# Nikon_PowerBoardV4.net
KiCad netlist of a schematic drawn in EAGLE
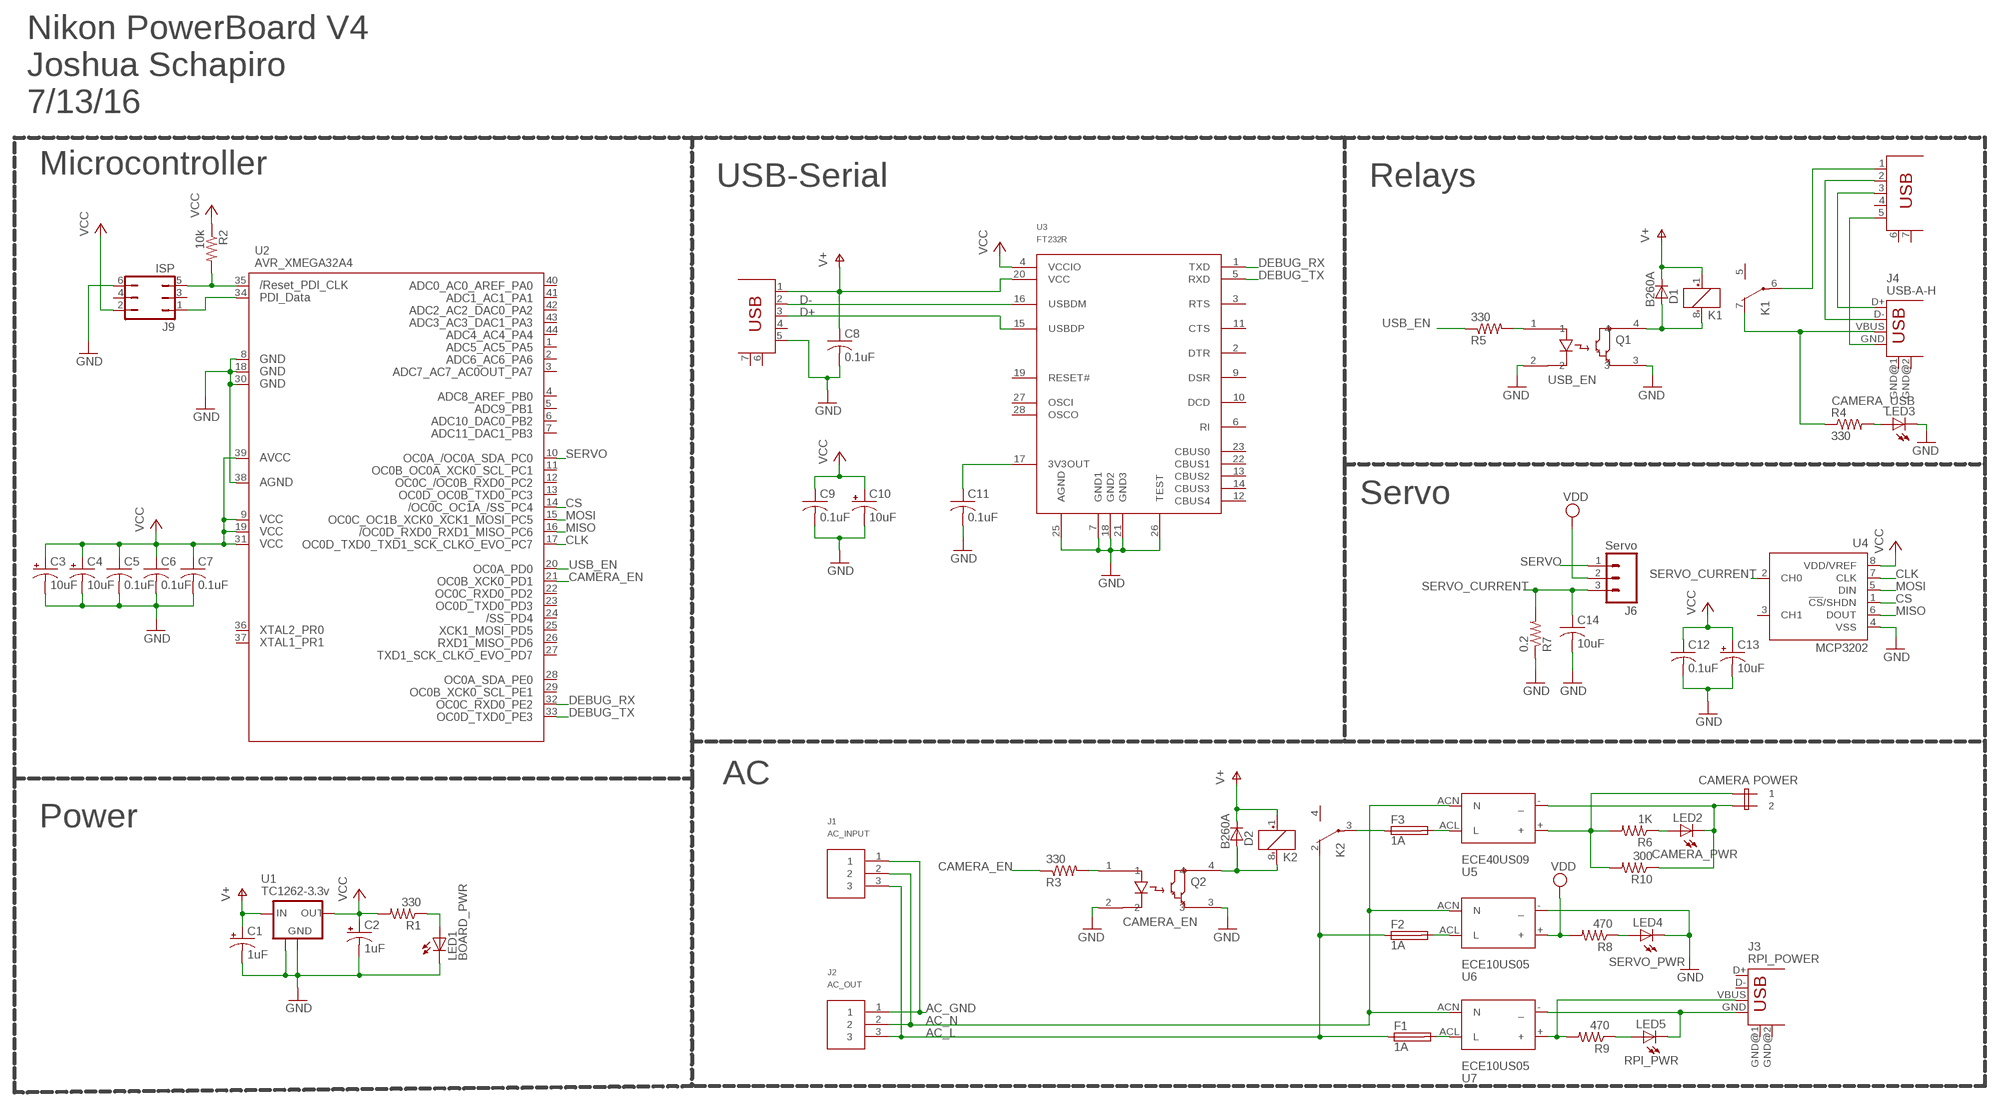
[diagram p0: schematic, sheet 1]

(export (version "E")
  (design (tool "Eeschema 10.0.6"))
  (components
    (comp (ref "C1")
      (value "1uF")
      (footprint "eagle-import:EIA3216")
      (libsource (lib "eagle-import") (part "CAP_POL1206"))
    )
    (comp (ref "C2")
      (value "1uF")
      (footprint "eagle-import:EIA3216")
      (libsource (lib "eagle-import") (part "CAP_POL1206"))
    )
    (comp (ref "C3")
      (value "10uF")
      (footprint "eagle-import:EIA3216")
      (libsource (lib "eagle-import") (part "CAP_POL1206"))
    )
    (comp (ref "C4")
      (value "10uF")
      (footprint "eagle-import:EIA3216")
      (libsource (lib "eagle-import") (part "CAP_POL1206"))
    )
    (comp (ref "C5")
      (value "0.1uF")
      (footprint "eagle-import:C0603")
      (libsource (lib "eagle-import") (part "C-USC0603"))
    )
    (comp (ref "C6")
      (value "0.1uF")
      (footprint "eagle-import:C0603")
      (libsource (lib "eagle-import") (part "resistor_C-USC0603"))
    )
    (comp (ref "C7")
      (value "0.1uF")
      (footprint "eagle-import:C0603")
      (libsource (lib "eagle-import") (part "resistor_C-USC0603"))
    )
    (comp (ref "C8")
      (value "0.1uF")
      (footprint "eagle-import:C0603")
      (libsource (lib "eagle-import") (part "resistor_C-USC0603"))
    )
    (comp (ref "C9")
      (value "0.1uF")
      (footprint "eagle-import:C0603")
      (libsource (lib "eagle-import") (part "resistor_C-USC0603"))
    )
    (comp (ref "C10")
      (value "10uF")
      (footprint "eagle-import:EIA3216")
      (libsource (lib "eagle-import") (part "CAP_POL1206"))
    )
    (comp (ref "C11")
      (value "0.1uF")
      (footprint "eagle-import:C0603")
      (libsource (lib "eagle-import") (part "resistor_C-USC0603"))
    )
    (comp (ref "C12")
      (value "0.1uF")
      (footprint "eagle-import:C0603")
      (libsource (lib "eagle-import") (part "resistor_C-USC0603"))
    )
    (comp (ref "C13")
      (value "10uF")
      (footprint "eagle-import:EIA3216")
      (libsource (lib "eagle-import") (part "CAP_POL1206"))
    )
    (comp (ref "C14")
      (value "10uF")
      (footprint "eagle-import:C1206")
      (libsource (lib "eagle-import") (part "resistor_C-USC1206"))
    )
    (comp (ref "D1")
      (value "B260A")
      (footprint "eagle-import:SMA-DIODE")
      (libsource (lib "eagle-import") (part "DIODESMA"))
    )
    (comp (ref "D2")
      (value "B260A")
      (footprint "eagle-import:SMA-DIODE")
      (libsource (lib "eagle-import") (part "DIODESMA"))
    )
    (comp (ref "F1")
      (value "1A")
      (footprint "eagle-import:19560")
      (libsource (lib "eagle-import") (part "19560"))
    )
    (comp (ref "F2")
      (value "1A")
      (footprint "eagle-import:19560")
      (libsource (lib "eagle-import") (part "19560"))
    )
    (comp (ref "F3")
      (value "1A")
      (footprint "eagle-import:19560")
      (libsource (lib "eagle-import") (part "19560"))
    )
    (comp (ref "J1")
      (value "AC_INPUT")
      (footprint "eagle-import:3-PIN-SCREW")
      (libsource (lib "eagle-import") (part "3-PIN-SCREW"))
    )
    (comp (ref "J2")
      (value "AC_OUT")
      (footprint "eagle-import:3-PIN-SCREW")
      (libsource (lib "eagle-import") (part "3-PIN-SCREW"))
    )
    (comp (ref "J3")
      (value "RPI_POWER")
      (footprint "eagle-import:USB-A-H")
      (libsource (lib "eagle-import") (part "USB-A-H"))
    )
    (comp (ref "J4")
      (value "USB-A-H")
      (footprint "eagle-import:USB-A-H")
      (libsource (lib "eagle-import") (part "USB-A-H"))
    )
    (comp (ref "J5")
      (value "CAMERA POWER")
      (footprint "eagle-import:2-PIN_SCREWTERM")
      (libsource (lib "eagle-import") (part "2-PIN_SCREWTERMINAL"))
    )
    (comp (ref "J6")
      (value "Servo")
      (footprint "eagle-import:1X03_LONGPADS")
      (libsource (lib "eagle-import") (part "M03LONGPADS"))
    )
    (comp (ref "J7")
      (value "MICRO-USB")
      (footprint "eagle-import:MICRO_USB_SM_W__TO_PINS")
      (libsource (lib "eagle-import") (part "MICRO-USBTO_SUPPORT"))
    )
    (comp (ref "J8")
      (value "MICRO-USB")
      (footprint "eagle-import:MICRO_USB_SM_W__TO_PINS")
      (libsource (lib "eagle-import") (part "MICRO-USBTO_SUPPORT"))
    )
    (comp (ref "J9")
      (value "ISP")
      (footprint "eagle-import:JP3Q")
      (libsource (lib "eagle-import") (part "JP3Q"))
    )
    (comp (ref "K1")
      (value "USB_EN")
      (footprint "eagle-import:G6K-2F")
      (libsource (lib "eagle-import") (part "G6K-2F"))
    )
    (comp (ref "K2")
      (value "CAMERA_EN")
      (footprint "eagle-import:G6K-2F")
      (libsource (lib "eagle-import") (part "G6K-2F"))
    )
    (comp (ref "LED1")
      (value "BOARD_PWR")
      (footprint "eagle-import:CHIPLED_0603")
      (libsource (lib "eagle-import") (part "LEDCHIPLED_0603"))
    )
    (comp (ref "LED2")
      (value "CAMERA_PWR")
      (footprint "eagle-import:CHIPLED_0603")
      (libsource (lib "eagle-import") (part "LEDCHIPLED_0603"))
    )
    (comp (ref "LED3")
      (value "CAMERA_USB")
      (footprint "eagle-import:CHIPLED_0603")
      (libsource (lib "eagle-import") (part "LEDCHIPLED_0603"))
    )
    (comp (ref "LED4")
      (value "SERVO_PWR")
      (footprint "eagle-import:CHIPLED_0603")
      (libsource (lib "eagle-import") (part "LEDCHIPLED_0603"))
    )
    (comp (ref "LED5")
      (value "RPI_PWR")
      (footprint "eagle-import:CHIPLED_0603")
      (libsource (lib "eagle-import") (part "LEDCHIPLED_0603"))
    )
    (comp (ref "Q1")
      (value "USB_EN")
      (footprint "eagle-import:4-PIN_MINI-FLAT")
      (libsource (lib "eagle-import") (part "OPTOISOLATOR_SINGLE"))
    )
    (comp (ref "Q2")
      (value "CAMERA_EN")
      (footprint "eagle-import:4-PIN_MINI-FLAT")
      (libsource (lib "eagle-import") (part "OPTOISOLATOR_SINGLE"))
    )
    (comp (ref "R1")
      (value "330")
      (footprint "eagle-import:R0603")
      (libsource (lib "eagle-import") (part "resistor_R-US_R0603"))
    )
    (comp (ref "R2")
      (value "10k")
      (footprint "eagle-import:R0603")
      (libsource (lib "eagle-import") (part "resistor_R-US_R0603"))
    )
    (comp (ref "R3")
      (value "330")
      (footprint "eagle-import:R0603")
      (libsource (lib "eagle-import") (part "resistor_R-US_R0603"))
    )
    (comp (ref "R4")
      (value "330")
      (footprint "eagle-import:R0603")
      (libsource (lib "eagle-import") (part "resistor_R-US_R0603"))
    )
    (comp (ref "R5")
      (value "330")
      (footprint "eagle-import:R0603")
      (libsource (lib "eagle-import") (part "resistor_R-US_R0603"))
    )
    (comp (ref "R6")
      (value "1K")
      (footprint "eagle-import:R0603")
      (libsource (lib "eagle-import") (part "resistor_R-US_R0603"))
    )
    (comp (ref "R7")
      (value "0.2")
      (footprint "eagle-import:R1206")
      (libsource (lib "eagle-import") (part "R-US_R1206"))
    )
    (comp (ref "R8")
      (value "470")
      (footprint "eagle-import:R0603")
      (libsource (lib "eagle-import") (part "resistor_R-US_R0603"))
    )
    (comp (ref "R9")
      (value "470")
      (footprint "eagle-import:R0603")
      (libsource (lib "eagle-import") (part "resistor_R-US_R0603"))
    )
    (comp (ref "R10")
      (value "300")
      (footprint "eagle-import:R2512")
      (libsource (lib "eagle-import") (part "resistor_R-US_R2512"))
    )
    (comp (ref "U1")
      (value "TC1262-3.3v")
      (footprint "eagle-import:SOT223")
      (libsource (lib "eagle-import") (part "REGULATOR"))
    )
    (comp (ref "U2")
      (value "AVR_XMEGA32A4")
      (footprint "eagle-import:TQFP44")
      (libsource (lib "eagle-import") (part "AVR_XMEGA_A4_44A"))
    )
    (comp (ref "U3")
      (value "FT232R")
      (footprint "eagle-import:SSOP28")
      (libsource (lib "eagle-import") (part "FT232R"))
    )
    (comp (ref "U4")
      (value "MCP3202")
      (footprint "eagle-import:SO-08")
      (libsource (lib "eagle-import") (part "MCP3202SN"))
    )
    (comp (ref "U5")
      (value "ECE40US09")
      (footprint "eagle-import:EC40")
      (libsource (lib "eagle-import") (part "AC_DC_CONVERTERUS09"))
    )
    (comp (ref "U6")
      (value "ECE10US05")
      (footprint "eagle-import:ECE10")
      (libsource (lib "eagle-import") (part "AC_DC_CONVERTERUS05"))
    )
    (comp (ref "U7")
      (value "ECE10US05")
      (footprint "eagle-import:ECE10")
      (libsource (lib "eagle-import") (part "AC_DC_CONVERTERUS05"))
    )
  )
  (nets
    (net (code "1") (name "/AC_GND") (class "Default")
      (node (ref "J1") (pin "1") (pinfunction "1_1") (pintype "bidirectional"))
      (node (ref "J2") (pin "1") (pinfunction "1_1") (pintype "bidirectional"))
    )
    (net (code "2") (name "/AC_L") (class "Default")
      (node (ref "F1") (pin "1") (pinfunction "1_1") (pintype "passive"))
      (node (ref "F2") (pin "1") (pinfunction "1_1") (pintype "passive"))
      (node (ref "J1") (pin "3") (pinfunction "3_3") (pintype "bidirectional"))
      (node (ref "J2") (pin "3") (pinfunction "3_3") (pintype "bidirectional"))
      (node (ref "K2") (pin "2") (pinfunction "O_2") (pintype "passive"))
    )
    (net (code "3") (name "/AC_N") (class "Default")
      (node (ref "J1") (pin "2") (pinfunction "2_2") (pintype "bidirectional"))
      (node (ref "J2") (pin "2") (pinfunction "2_2") (pintype "bidirectional"))
      (node (ref "U5") (pin "ACN") (pinfunction "N_ACN") (pintype "bidirectional"))
      (node (ref "U6") (pin "ACN") (pinfunction "N_ACN") (pintype "bidirectional"))
      (node (ref "U7") (pin "ACN") (pinfunction "N_ACN") (pintype "bidirectional"))
    )
    (net (code "4") (name "/CAMERA_EN") (class "Default")
      (node (ref "R3") (pin "1") (pinfunction "1_1") (pintype "passive"))
      (node (ref "U2") (pin "21") (pinfunction "PD1_21") (pintype "bidirectional"))
    )
    (net (code "5") (name "/CLK") (class "Default")
      (node (ref "U2") (pin "17") (pinfunction "PC7_17") (pintype "bidirectional"))
      (node (ref "U4") (pin "7") (pinfunction "CLK_7") (pintype "input"))
    )
    (net (code "6") (name "/CS") (class "Default")
      (node (ref "U2") (pin "14") (pinfunction "PC4_14") (pintype "bidirectional"))
      (node (ref "U4") (pin "1") (pinfunction "~{CS}/SHDN_1") (pintype "input"))
    )
    (net (code "7") (name "/D+") (class "Default")
      (node (ref "J8") (pin "3") (pinfunction "D+_3") (pintype "bidirectional"))
      (node (ref "U3") (pin "15") (pinfunction "USBDP_15") (pintype "bidirectional"))
    )
    (net (code "8") (name "/D-") (class "Default")
      (node (ref "J8") (pin "2") (pinfunction "D-_2") (pintype "bidirectional"))
      (node (ref "U3") (pin "16") (pinfunction "USBDM_16") (pintype "bidirectional"))
    )
    (net (code "9") (name "/DEBUG_RX") (class "Default")
      (node (ref "U2") (pin "32") (pinfunction "PE2_32") (pintype "bidirectional"))
      (node (ref "U3") (pin "1") (pinfunction "TXD_1") (pintype "bidirectional"))
    )
    (net (code "10") (name "/DEBUG_TX") (class "Default")
      (node (ref "U2") (pin "33") (pinfunction "PE3_33") (pintype "bidirectional"))
      (node (ref "U3") (pin "5") (pinfunction "RXD_5") (pintype "bidirectional"))
    )
    (net (code "11") (name "/MISO") (class "Default")
      (node (ref "U2") (pin "16") (pinfunction "PC6_16") (pintype "bidirectional"))
      (node (ref "U4") (pin "6") (pinfunction "DOUT_6") (pintype "input"))
    )
    (net (code "12") (name "/MOSI") (class "Default")
      (node (ref "U2") (pin "15") (pinfunction "PC5_15") (pintype "bidirectional"))
      (node (ref "U4") (pin "5") (pinfunction "DIN_5") (pintype "input"))
    )
    (net (code "13") (name "/SERVO") (class "Default")
      (node (ref "J6") (pin "1") (pinfunction "1_1") (pintype "passive"))
      (node (ref "U2") (pin "10") (pinfunction "PC0_10") (pintype "bidirectional"))
    )
    (net (code "14") (name "/SERVO_CURRENT") (class "Default")
      (node (ref "C14") (pin "1") (pinfunction "1_1") (pintype "passive"))
      (node (ref "J6") (pin "3") (pinfunction "3_3") (pintype "passive"))
      (node (ref "R7") (pin "2") (pinfunction "2_2") (pintype "passive"))
      (node (ref "U4") (pin "2") (pinfunction "CH0_2") (pintype "input"))
    )
    (net (code "15") (name "/USB_EN") (class "Default")
      (node (ref "R5") (pin "1") (pinfunction "1_1") (pintype "passive"))
      (node (ref "U2") (pin "20") (pinfunction "PD0_20") (pintype "bidirectional"))
    )
    (net (code "16") (name "GND") (class "Default")
      (node (ref "C1") (pin "C") (pinfunction "-_C") (pintype "passive"))
      (node (ref "C10") (pin "C") (pinfunction "-_C") (pintype "passive"))
      (node (ref "C11") (pin "2") (pinfunction "2_2") (pintype "passive"))
      (node (ref "C12") (pin "2") (pinfunction "2_2") (pintype "passive"))
      (node (ref "C13") (pin "C") (pinfunction "-_C") (pintype "passive"))
      (node (ref "C14") (pin "2") (pinfunction "2_2") (pintype "passive"))
      (node (ref "C2") (pin "C") (pinfunction "-_C") (pintype "passive"))
      (node (ref "C3") (pin "C") (pinfunction "-_C") (pintype "passive"))
      (node (ref "C4") (pin "C") (pinfunction "-_C") (pintype "passive"))
      (node (ref "C5") (pin "2") (pinfunction "2_2") (pintype "passive"))
      (node (ref "C6") (pin "2") (pinfunction "2_2") (pintype "passive"))
      (node (ref "C7") (pin "2") (pinfunction "2_2") (pintype "passive"))
      (node (ref "C8") (pin "2") (pinfunction "2_2") (pintype "passive"))
      (node (ref "C9") (pin "2") (pinfunction "2_2") (pintype "passive"))
      (node (ref "J8") (pin "5") (pinfunction "GND_5") (pintype "bidirectional"))
      (node (ref "J9") (pin "6") (pinfunction "6_6") (pintype "passive"))
      (node (ref "LED1") (pin "C") (pinfunction "C_C") (pintype "passive"))
      (node (ref "LED3") (pin "C") (pinfunction "C_C") (pintype "passive"))
      (node (ref "LED4") (pin "C") (pinfunction "C_C") (pintype "passive"))
      (node (ref "Q1") (pin "2") (pinfunction "2_2") (pintype "bidirectional"))
      (node (ref "Q1") (pin "3") (pinfunction "3_3") (pintype "bidirectional"))
      (node (ref "Q2") (pin "2") (pinfunction "2_2") (pintype "bidirectional"))
      (node (ref "Q2") (pin "3") (pinfunction "3_3") (pintype "bidirectional"))
      (node (ref "R7") (pin "1") (pinfunction "1_1") (pintype "passive"))
      (node (ref "U1") (pin "2") (pinfunction "GND_2") (pintype "bidirectional"))
      (node (ref "U1") (pin "4") (pinfunction "GND1_4") (pintype "bidirectional"))
      (node (ref "U2") (pin "18") (pinfunction "GND2_18") (pintype "bidirectional"))
      (node (ref "U2") (pin "30") (pinfunction "GND3_30") (pintype "bidirectional"))
      (node (ref "U2") (pin "38") (pinfunction "AGND_38") (pintype "bidirectional"))
      (node (ref "U2") (pin "8") (pinfunction "GND1_8") (pintype "bidirectional"))
      (node (ref "U3") (pin "18") (pinfunction "GND2_18") (pintype "bidirectional"))
      (node (ref "U3") (pin "21") (pinfunction "GND3_21") (pintype "bidirectional"))
      (node (ref "U3") (pin "25") (pinfunction "AGND_25") (pintype "bidirectional"))
      (node (ref "U3") (pin "26") (pinfunction "TEST_26") (pintype "bidirectional"))
      (node (ref "U3") (pin "7") (pinfunction "GND1_7") (pintype "bidirectional"))
      (node (ref "U4") (pin "4") (pinfunction "VSS_4") (pintype "input"))
      (node (ref "U6") (pin "-") (pinfunction "__-") (pintype "bidirectional"))
    )
    (net (code "17") (name "Net-(J3-PadVBUS)") (class "Default")
      (node (ref "J3") (pin "VBUS") (pinfunction "VBUS_VBUS") (pintype "bidirectional"))
      (node (ref "R9") (pin "2") (pinfunction "2_2") (pintype "passive"))
      (node (ref "U7") (pin "+") (pinfunction "+_+") (pintype "bidirectional"))
    )
    (net (code "18") (name "Net-(J5-1)") (class "Default")
      (node (ref "J5") (pin "P$1") (pinfunction "1_P$1") (pintype "bidirectional"))
      (node (ref "R10") (pin "2") (pinfunction "2_2") (pintype "passive"))
      (node (ref "R6") (pin "2") (pinfunction "2_2") (pintype "passive"))
      (node (ref "U5") (pin "+") (pinfunction "+_+") (pintype "bidirectional"))
    )
    (net (code "19") (name "Net-(J5-2)") (class "Default")
      (node (ref "J5") (pin "P$2") (pinfunction "2_P$2") (pintype "bidirectional"))
      (node (ref "LED2") (pin "C") (pinfunction "C_C") (pintype "passive"))
      (node (ref "R10") (pin "1") (pinfunction "1_1") (pintype "passive"))
      (node (ref "U5") (pin "-") (pinfunction "__-") (pintype "bidirectional"))
    )
    (net (code "20") (name "Net-(J7-D+)") (class "Default")
      (node (ref "J4") (pin "D+") (pinfunction "D+_D+") (pintype "bidirectional"))
      (node (ref "J7") (pin "3") (pinfunction "D+_3") (pintype "bidirectional"))
    )
    (net (code "21") (name "Net-(J7-D-)") (class "Default")
      (node (ref "J4") (pin "D-") (pinfunction "D-_D-") (pintype "bidirectional"))
      (node (ref "J7") (pin "2") (pinfunction "D-_2") (pintype "bidirectional"))
    )
    (net (code "22") (name "Net-(J7-GND)") (class "Default")
      (node (ref "J4") (pin "GND") (pinfunction "GND_GND") (pintype "bidirectional"))
      (node (ref "J7") (pin "5") (pinfunction "GND_5") (pintype "bidirectional"))
    )
    (net (code "23") (name "Net-(J7-VBUS)") (class "Default")
      (node (ref "J7") (pin "1") (pinfunction "VBUS_1") (pintype "bidirectional"))
      (node (ref "K1") (pin "6") (pinfunction "P_6") (pintype "passive"))
    )
    (net (code "24") (name "Net-(K1A--)") (class "Default")
      (node (ref "D1") (pin "A") (pinfunction "A_A") (pintype "passive"))
      (node (ref "K1") (pin "8") (pinfunction "-_8") (pintype "passive"))
      (node (ref "Q1") (pin "4") (pinfunction "4_4") (pintype "bidirectional"))
    )
    (net (code "25") (name "Net-(K1C-O)") (class "Default")
      (node (ref "J4") (pin "VBUS") (pinfunction "VBUS_VBUS") (pintype "bidirectional"))
      (node (ref "K1") (pin "7") (pinfunction "O_7") (pintype "passive"))
      (node (ref "R4") (pin "1") (pinfunction "1_1") (pintype "passive"))
    )
    (net (code "26") (name "Net-(K2A--)") (class "Default")
      (node (ref "D2") (pin "A") (pinfunction "A_A") (pintype "passive"))
      (node (ref "K2") (pin "8") (pinfunction "-_8") (pintype "passive"))
      (node (ref "Q2") (pin "4") (pinfunction "4_4") (pintype "bidirectional"))
    )
    (net (code "27") (name "Net-(K2B-P)") (class "Default")
      (node (ref "F3") (pin "1") (pinfunction "1_1") (pintype "passive"))
      (node (ref "K2") (pin "3") (pinfunction "P_3") (pintype "passive"))
    )
    (net (code "28") (name "Net-(LED1-PadA)") (class "Default")
      (node (ref "LED1") (pin "A") (pinfunction "A_A") (pintype "passive"))
      (node (ref "R1") (pin "1") (pinfunction "1_1") (pintype "passive"))
    )
    (net (code "29") (name "Net-(LED2-PadA)") (class "Default")
      (node (ref "LED2") (pin "A") (pinfunction "A_A") (pintype "passive"))
      (node (ref "R6") (pin "1") (pinfunction "1_1") (pintype "passive"))
    )
    (net (code "30") (name "Net-(LED3-PadA)") (class "Default")
      (node (ref "LED3") (pin "A") (pinfunction "A_A") (pintype "passive"))
      (node (ref "R4") (pin "2") (pinfunction "2_2") (pintype "passive"))
    )
    (net (code "31") (name "Net-(LED4-PadA)") (class "Default")
      (node (ref "LED4") (pin "A") (pinfunction "A_A") (pintype "passive"))
      (node (ref "R8") (pin "1") (pinfunction "1_1") (pintype "passive"))
    )
    (net (code "32") (name "Net-(LED5-PadA)") (class "Default")
      (node (ref "LED5") (pin "A") (pinfunction "A_A") (pintype "passive"))
      (node (ref "R9") (pin "1") (pinfunction "1_1") (pintype "passive"))
    )
    (net (code "33") (name "Net-(Q1-Pad1)") (class "Default")
      (node (ref "Q1") (pin "1") (pinfunction "1_1") (pintype "bidirectional"))
      (node (ref "R5") (pin "2") (pinfunction "2_2") (pintype "passive"))
    )
    (net (code "34") (name "Net-(Q2-Pad1)") (class "Default")
      (node (ref "Q2") (pin "1") (pinfunction "1_1") (pintype "bidirectional"))
      (node (ref "R3") (pin "2") (pinfunction "2_2") (pintype "passive"))
    )
    (net (code "35") (name "Net-(U2-PDI_DATA)") (class "Default")
      (node (ref "J9") (pin "1") (pinfunction "1_1") (pintype "passive"))
      (node (ref "U2") (pin "34") (pinfunction "PDI_DATA_34") (pintype "bidirectional"))
    )
    (net (code "36") (name "Net-(U2-RESET)") (class "Default")
      (node (ref "J9") (pin "5") (pinfunction "5_5") (pintype "passive"))
      (node (ref "R2") (pin "2") (pinfunction "2_2") (pintype "passive"))
      (node (ref "U2") (pin "35") (pinfunction "RESET_35") (pintype "bidirectional"))
    )
    (net (code "37") (name "Net-(U3-3V3OUT)") (class "Default")
      (node (ref "C11") (pin "1") (pinfunction "1_1") (pintype "passive"))
      (node (ref "U3") (pin "17") (pinfunction "3V3OUT_17") (pintype "bidirectional"))
    )
    (net (code "38") (name "Net-(U5-L)") (class "Default")
      (node (ref "F3") (pin "2") (pinfunction "2_2") (pintype "passive"))
      (node (ref "U5") (pin "ACL") (pinfunction "L_ACL") (pintype "bidirectional"))
    )
    (net (code "39") (name "Net-(U6-L)") (class "Default")
      (node (ref "F2") (pin "2") (pinfunction "2_2") (pintype "passive"))
      (node (ref "U6") (pin "ACL") (pinfunction "L_ACL") (pintype "bidirectional"))
    )
    (net (code "40") (name "Net-(U7-L)") (class "Default")
      (node (ref "F1") (pin "2") (pinfunction "2_2") (pintype "passive"))
      (node (ref "U7") (pin "ACL") (pinfunction "L_ACL") (pintype "bidirectional"))
    )
    (net (code "41") (name "Net-(U7-_)") (class "Default")
      (node (ref "J3") (pin "GND") (pinfunction "GND_GND") (pintype "bidirectional"))
      (node (ref "LED5") (pin "C") (pinfunction "C_C") (pintype "passive"))
      (node (ref "U7") (pin "-") (pinfunction "__-") (pintype "bidirectional"))
    )
    (net (code "42") (name "V+") (class "Default")
      (node (ref "C1") (pin "A") (pinfunction "+_A") (pintype "passive"))
      (node (ref "C8") (pin "1") (pinfunction "1_1") (pintype "passive"))
      (node (ref "D1") (pin "C") (pinfunction "C_C") (pintype "passive"))
      (node (ref "D2") (pin "C") (pinfunction "C_C") (pintype "passive"))
      (node (ref "J8") (pin "1") (pinfunction "VBUS_1") (pintype "bidirectional"))
      (node (ref "K1") (pin "1") (pinfunction "+_1") (pintype "passive"))
      (node (ref "K2") (pin "1") (pinfunction "+_1") (pintype "passive"))
      (node (ref "U1") (pin "1") (pinfunction "IN_1") (pintype "bidirectional"))
      (node (ref "U3") (pin "20") (pinfunction "VCC_20") (pintype "bidirectional"))
    )
    (net (code "43") (name "VCC") (class "Default")
      (node (ref "C10") (pin "A") (pinfunction "+_A") (pintype "passive"))
      (node (ref "C12") (pin "1") (pinfunction "1_1") (pintype "passive"))
      (node (ref "C13") (pin "A") (pinfunction "+_A") (pintype "passive"))
      (node (ref "C2") (pin "A") (pinfunction "+_A") (pintype "passive"))
      (node (ref "C3") (pin "A") (pinfunction "+_A") (pintype "passive"))
      (node (ref "C4") (pin "A") (pinfunction "+_A") (pintype "passive"))
      (node (ref "C5") (pin "1") (pinfunction "1_1") (pintype "passive"))
      (node (ref "C6") (pin "1") (pinfunction "1_1") (pintype "passive"))
      (node (ref "C7") (pin "1") (pinfunction "1_1") (pintype "passive"))
      (node (ref "C9") (pin "1") (pinfunction "1_1") (pintype "passive"))
      (node (ref "J9") (pin "2") (pinfunction "2_2") (pintype "passive"))
      (node (ref "R1") (pin "2") (pinfunction "2_2") (pintype "passive"))
      (node (ref "R2") (pin "1") (pinfunction "1_1") (pintype "passive"))
      (node (ref "U1") (pin "3") (pinfunction "OUT_3") (pintype "bidirectional"))
      (node (ref "U2") (pin "19") (pinfunction "VCC2_19") (pintype "bidirectional"))
      (node (ref "U2") (pin "31") (pinfunction "VCC3_31") (pintype "bidirectional"))
      (node (ref "U2") (pin "39") (pinfunction "AVCC_39") (pintype "bidirectional"))
      (node (ref "U2") (pin "9") (pinfunction "VCC1_9") (pintype "bidirectional"))
      (node (ref "U3") (pin "4") (pinfunction "VCCIO_4") (pintype "bidirectional"))
      (node (ref "U4") (pin "8") (pinfunction "VDD/VREF_8") (pintype "input"))
    )
    (net (code "44") (name "VDD") (class "Default")
      (node (ref "J6") (pin "2") (pinfunction "2_2") (pintype "passive"))
      (node (ref "R8") (pin "2") (pinfunction "2_2") (pintype "passive"))
      (node (ref "U6") (pin "+") (pinfunction "+_+") (pintype "bidirectional"))
    )
    (net (code "45") (name "unconnected-(J3-GND-PadGND@1)") (class "Default")
      (node (ref "J3") (pin "GND@1") (pinfunction "GND_GND@1") (pintype "bidirectional"))
    )
    (net (code "46") (name "unconnected-(J3-GND-PadGND@2)") (class "Default")
      (node (ref "J3") (pin "GND@2") (pinfunction "GND_GND@2") (pintype "bidirectional"))
    )
    (net (code "47") (name "unconnected-(J3-PadD+)") (class "Default")
      (node (ref "J3") (pin "D+") (pinfunction "D+_D+") (pintype "bidirectional"))
    )
    (net (code "48") (name "unconnected-(J3-PadD-)") (class "Default")
      (node (ref "J3") (pin "D-") (pinfunction "D-_D-") (pintype "bidirectional"))
    )
    (net (code "49") (name "unconnected-(J4-GND-PadGND@1)") (class "Default")
      (node (ref "J4") (pin "GND@1") (pinfunction "GND_GND@1") (pintype "bidirectional"))
    )
    (net (code "50") (name "unconnected-(J4-GND-PadGND@2)") (class "Default")
      (node (ref "J4") (pin "GND@2") (pinfunction "GND_GND@2") (pintype "bidirectional"))
    )
    (net (code "51") (name "unconnected-(J7-ID-Pad4)") (class "Default")
      (node (ref "J7") (pin "4") (pinfunction "ID_4") (pintype "bidirectional"))
    )
    (net (code "52") (name "unconnected-(J7-MTN3-Pad6)") (class "Default")
      (node (ref "J7") (pin "6") (pinfunction "MTN3_6") (pintype "bidirectional"))
    )
    (net (code "53") (name "unconnected-(J7-MTN4-Pad7)") (class "Default")
      (node (ref "J7") (pin "7") (pinfunction "MTN4_7") (pintype "bidirectional"))
    )
    (net (code "54") (name "unconnected-(J8-ID-Pad4)") (class "Default")
      (node (ref "J8") (pin "4") (pinfunction "ID_4") (pintype "bidirectional"))
    )
    (net (code "55") (name "unconnected-(J8-MTN3-Pad6)") (class "Default")
      (node (ref "J8") (pin "6") (pinfunction "MTN3_6") (pintype "bidirectional"))
    )
    (net (code "56") (name "unconnected-(J8-MTN4-Pad7)") (class "Default")
      (node (ref "J8") (pin "7") (pinfunction "MTN4_7") (pintype "bidirectional"))
    )
    (net (code "57") (name "unconnected-(J9-Pad3)") (class "Default")
      (node (ref "J9") (pin "3") (pinfunction "3_3") (pintype "passive"))
    )
    (net (code "58") (name "unconnected-(J9-Pad4)") (class "Default")
      (node (ref "J9") (pin "4") (pinfunction "4_4") (pintype "passive"))
    )
    (net (code "59") (name "unconnected-(K1C-S-Pad5)") (class "Default")
      (node (ref "K1") (pin "5") (pinfunction "S_5") (pintype "passive"))
    )
    (net (code "60") (name "unconnected-(K2B-S-Pad4)") (class "Default")
      (node (ref "K2") (pin "4") (pinfunction "S_4") (pintype "passive"))
    )
    (net (code "61") (name "unconnected-(U2-PA0-Pad40)") (class "Default")
      (node (ref "U2") (pin "40") (pinfunction "PA0_40") (pintype "bidirectional"))
    )
    (net (code "62") (name "unconnected-(U2-PA1-Pad41)") (class "Default")
      (node (ref "U2") (pin "41") (pinfunction "PA1_41") (pintype "bidirectional"))
    )
    (net (code "63") (name "unconnected-(U2-PA2-Pad42)") (class "Default")
      (node (ref "U2") (pin "42") (pinfunction "PA2_42") (pintype "bidirectional"))
    )
    (net (code "64") (name "unconnected-(U2-PA3-Pad43)") (class "Default")
      (node (ref "U2") (pin "43") (pinfunction "PA3_43") (pintype "bidirectional"))
    )
    (net (code "65") (name "unconnected-(U2-PA4-Pad44)") (class "Default")
      (node (ref "U2") (pin "44") (pinfunction "PA4_44") (pintype "bidirectional"))
    )
    (net (code "66") (name "unconnected-(U2-PA5-Pad1)") (class "Default")
      (node (ref "U2") (pin "1") (pinfunction "PA5_1") (pintype "bidirectional"))
    )
    (net (code "67") (name "unconnected-(U2-PA6-Pad2)") (class "Default")
      (node (ref "U2") (pin "2") (pinfunction "PA6_2") (pintype "bidirectional"))
    )
    (net (code "68") (name "unconnected-(U2-PA7-Pad3)") (class "Default")
      (node (ref "U2") (pin "3") (pinfunction "PA7_3") (pintype "bidirectional"))
    )
    (net (code "69") (name "unconnected-(U2-PB0-Pad4)") (class "Default")
      (node (ref "U2") (pin "4") (pinfunction "PB0_4") (pintype "bidirectional"))
    )
    (net (code "70") (name "unconnected-(U2-PB1-Pad5)") (class "Default")
      (node (ref "U2") (pin "5") (pinfunction "PB1_5") (pintype "bidirectional"))
    )
    (net (code "71") (name "unconnected-(U2-PB2-Pad6)") (class "Default")
      (node (ref "U2") (pin "6") (pinfunction "PB2_6") (pintype "bidirectional"))
    )
    (net (code "72") (name "unconnected-(U2-PB3-Pad7)") (class "Default")
      (node (ref "U2") (pin "7") (pinfunction "PB3_7") (pintype "bidirectional"))
    )
    (net (code "73") (name "unconnected-(U2-PC1-Pad11)") (class "Default")
      (node (ref "U2") (pin "11") (pinfunction "PC1_11") (pintype "bidirectional"))
    )
    (net (code "74") (name "unconnected-(U2-PC2-Pad12)") (class "Default")
      (node (ref "U2") (pin "12") (pinfunction "PC2_12") (pintype "bidirectional"))
    )
    (net (code "75") (name "unconnected-(U2-PC3-Pad13)") (class "Default")
      (node (ref "U2") (pin "13") (pinfunction "PC3_13") (pintype "bidirectional"))
    )
    (net (code "76") (name "unconnected-(U2-PD2-Pad22)") (class "Default")
      (node (ref "U2") (pin "22") (pinfunction "PD2_22") (pintype "bidirectional"))
    )
    (net (code "77") (name "unconnected-(U2-PD3-Pad23)") (class "Default")
      (node (ref "U2") (pin "23") (pinfunction "PD3_23") (pintype "bidirectional"))
    )
    (net (code "78") (name "unconnected-(U2-PD4-Pad24)") (class "Default")
      (node (ref "U2") (pin "24") (pinfunction "PD4_24") (pintype "bidirectional"))
    )
    (net (code "79") (name "unconnected-(U2-PD5-Pad25)") (class "Default")
      (node (ref "U2") (pin "25") (pinfunction "PD5_25") (pintype "bidirectional"))
    )
    (net (code "80") (name "unconnected-(U2-PD6-Pad26)") (class "Default")
      (node (ref "U2") (pin "26") (pinfunction "PD6_26") (pintype "bidirectional"))
    )
    (net (code "81") (name "unconnected-(U2-PD7-Pad27)") (class "Default")
      (node (ref "U2") (pin "27") (pinfunction "PD7_27") (pintype "bidirectional"))
    )
    (net (code "82") (name "unconnected-(U2-PE0-Pad28)") (class "Default")
      (node (ref "U2") (pin "28") (pinfunction "PE0_28") (pintype "bidirectional"))
    )
    (net (code "83") (name "unconnected-(U2-PE1-Pad29)") (class "Default")
      (node (ref "U2") (pin "29") (pinfunction "PE1_29") (pintype "bidirectional"))
    )
    (net (code "84") (name "unconnected-(U2-PR0-Pad36)") (class "Default")
      (node (ref "U2") (pin "36") (pinfunction "PR0_36") (pintype "bidirectional"))
    )
    (net (code "85") (name "unconnected-(U2-PR1-Pad37)") (class "Default")
      (node (ref "U2") (pin "37") (pinfunction "PR1_37") (pintype "bidirectional"))
    )
    (net (code "86") (name "unconnected-(U3-CBUS0-Pad23)") (class "Default")
      (node (ref "U3") (pin "23") (pinfunction "CBUS0_23") (pintype "bidirectional"))
    )
    (net (code "87") (name "unconnected-(U3-CBUS1-Pad22)") (class "Default")
      (node (ref "U3") (pin "22") (pinfunction "CBUS1_22") (pintype "bidirectional"))
    )
    (net (code "88") (name "unconnected-(U3-CBUS2-Pad13)") (class "Default")
      (node (ref "U3") (pin "13") (pinfunction "CBUS2_13") (pintype "bidirectional"))
    )
    (net (code "89") (name "unconnected-(U3-CBUS3-Pad14)") (class "Default")
      (node (ref "U3") (pin "14") (pinfunction "CBUS3_14") (pintype "bidirectional"))
    )
    (net (code "90") (name "unconnected-(U3-CBUS4-Pad12)") (class "Default")
      (node (ref "U3") (pin "12") (pinfunction "CBUS4_12") (pintype "bidirectional"))
    )
    (net (code "91") (name "unconnected-(U3-CTS-Pad11)") (class "Default")
      (node (ref "U3") (pin "11") (pinfunction "CTS_11") (pintype "bidirectional"))
    )
    (net (code "92") (name "unconnected-(U3-DCD-Pad10)") (class "Default")
      (node (ref "U3") (pin "10") (pinfunction "DCD_10") (pintype "bidirectional"))
    )
    (net (code "93") (name "unconnected-(U3-DSR-Pad9)") (class "Default")
      (node (ref "U3") (pin "9") (pinfunction "DSR_9") (pintype "bidirectional"))
    )
    (net (code "94") (name "unconnected-(U3-DTR-Pad2)") (class "Default")
      (node (ref "U3") (pin "2") (pinfunction "DTR_2") (pintype "bidirectional"))
    )
    (net (code "95") (name "unconnected-(U3-OSCI-Pad27)") (class "Default")
      (node (ref "U3") (pin "27") (pinfunction "OSCI_27") (pintype "bidirectional"))
    )
    (net (code "96") (name "unconnected-(U3-OSCO-Pad28)") (class "Default")
      (node (ref "U3") (pin "28") (pinfunction "OSCO_28") (pintype "bidirectional"))
    )
    (net (code "97") (name "unconnected-(U3-RESET#-Pad19)") (class "Default")
      (node (ref "U3") (pin "19") (pinfunction "RESET#_19") (pintype "bidirectional"))
    )
    (net (code "98") (name "unconnected-(U3-RI-Pad6)") (class "Default")
      (node (ref "U3") (pin "6") (pinfunction "RI_6") (pintype "bidirectional"))
    )
    (net (code "99") (name "unconnected-(U3-RTS-Pad3)") (class "Default")
      (node (ref "U3") (pin "3") (pinfunction "RTS_3") (pintype "bidirectional"))
    )
    (net (code "100") (name "unconnected-(U4-CH1-Pad3)") (class "Default")
      (node (ref "U4") (pin "3") (pinfunction "CH1_3") (pintype "input"))
    )
  )
)
